# Main.net
KiCad netlist of a schematic drawn in Altium Designer
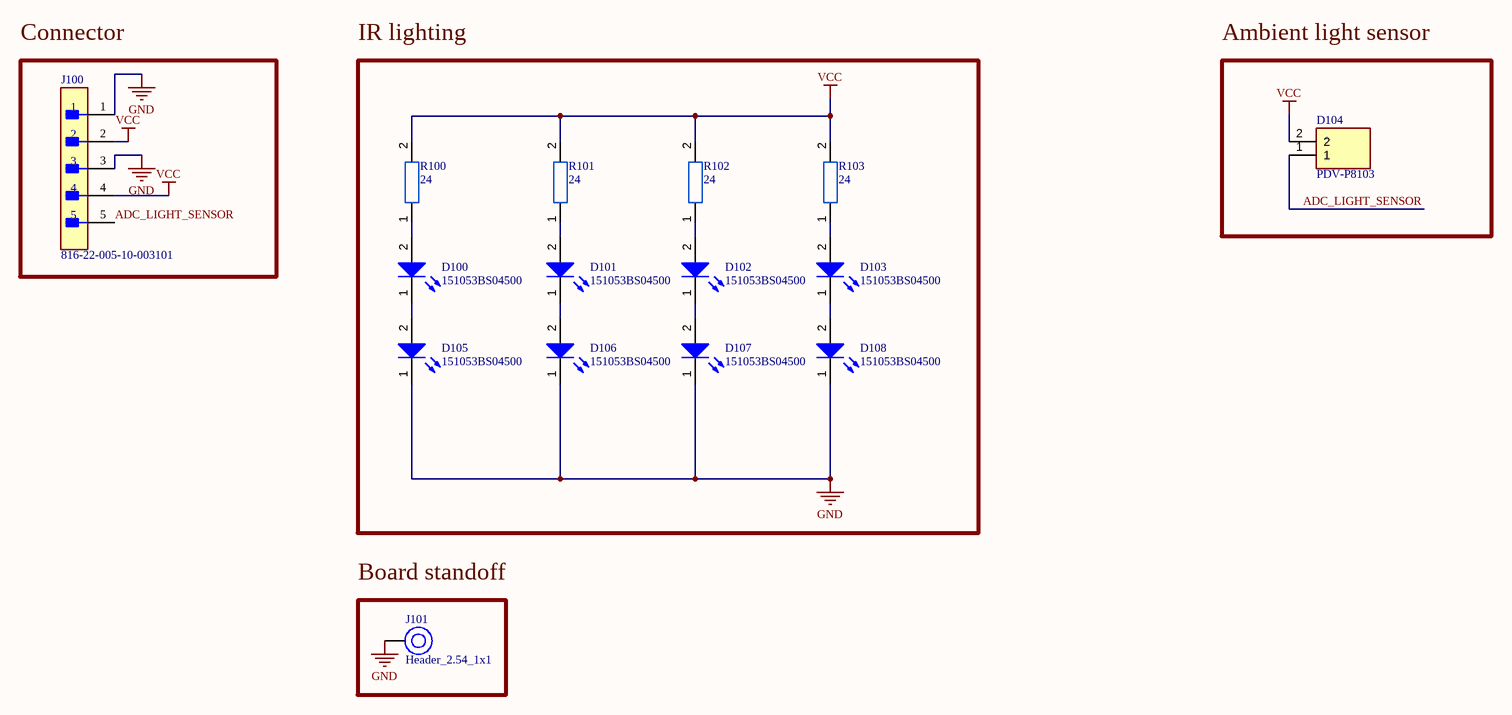
[diagram p0: Main.SchDoc]

(export (version "E")
  (design (tool "Eeschema 10.0.6"))
  (components
    (comp (ref "D100")
      (value "151053BS04500")
      (footprint "WL-TMRW_D5.8H11.7")
      (libsource (lib "Altium Content Vault") (part "LED_Blue_2A-1K"))
    )
    (comp (ref "D101")
      (value "151053BS04500")
      (footprint "WL-TMRW_D5.8H11.7")
      (libsource (lib "Altium Content Vault") (part "LED_Blue_2A-1K"))
    )
    (comp (ref "D102")
      (value "151053BS04500")
      (footprint "WL-TMRW_D5.8H11.7")
      (libsource (lib "Altium Content Vault") (part "LED_Blue_2A-1K"))
    )
    (comp (ref "D103")
      (value "151053BS04500")
      (footprint "WL-TMRW_D5.8H11.7")
      (description "https://www.lemona.lt/sviesos-diodas-o5mm-ir-skaidrus-30.html")
      (libsource (lib "Altium Content Vault") (part "LED_Blue_2A-1K"))
    )
    (comp (ref "D104")
      (value "PDV-P8103")
      (footprint "SamacSys:PDVP8103")
      (libsource (lib "*") (part "PDV-P8103"))
    )
    (comp (ref "D105")
      (value "151053BS04500")
      (footprint "WL-TMRW_D5.8H11.7")
      (libsource (lib "Altium Content Vault") (part "LED_Blue_2A-1K"))
    )
    (comp (ref "D106")
      (value "151053BS04500")
      (footprint "WL-TMRW_D5.8H11.7")
      (libsource (lib "Altium Content Vault") (part "LED_Blue_2A-1K"))
    )
    (comp (ref "D107")
      (value "151053BS04500")
      (footprint "WL-TMRW_D5.8H11.7")
      (libsource (lib "Altium Content Vault") (part "LED_Blue_2A-1K"))
    )
    (comp (ref "D108")
      (value "151053BS04500")
      (footprint "WL-TMRW_D5.8H11.7")
      (libsource (lib "Altium Content Vault") (part "LED_Blue_2A-1K"))
    )
    (comp (ref "J100")
      (value "816-22-005-10-003101")
      (footprint "FP-816-22-005-10-003101-MFG")
      (description "CONN SPRING PISTON 5POS PCB")
      (libsource (lib "Altium Content Vault") (part "bf93c07fd2649a848d0ec8585582aab"))
    )
    (comp (ref "J101")
      (value "Header_2.54_1x1")
      (footprint "HEADER_2.54_1x1")
      (libsource (lib "Schlib1") (part "Header_2.54_1x1"))
    )
    (comp (ref "R100")
      (value "24")
      (footprint "0402_footprint")
      (description "0402 resistor")
      (libsource (lib "Schlib1") (part "Resistor_0402"))
    )
    (comp (ref "R101")
      (value "24")
      (footprint "0402_footprint")
      (description "0402 resistor")
      (libsource (lib "Schlib1") (part "Resistor_0402"))
    )
    (comp (ref "R102")
      (value "24")
      (footprint "0402_footprint")
      (description "0402 resistor")
      (libsource (lib "Schlib1") (part "Resistor_0402"))
    )
    (comp (ref "R103")
      (value "24")
      (footprint "0402_footprint")
      (description "0402 resistor")
      (libsource (lib "Schlib1") (part "Resistor_0402"))
    )
  )
  (nets
    (net (code "1") (name "/ADC_LIGHT_SENSOR") (class "Default")
      (node (ref "D104") (pin "1") (pinfunction "1_1") (pintype "passive"))
      (node (ref "J100") (pin "5") (pinfunction "5_5") (pintype "passive"))
    )
    (net (code "2") (name "GND") (class "Default")
      (node (ref "D105") (pin "1") (pinfunction "K_1") (pintype "passive"))
      (node (ref "D106") (pin "1") (pinfunction "K_1") (pintype "passive"))
      (node (ref "D107") (pin "1") (pinfunction "K_1") (pintype "passive"))
      (node (ref "D108") (pin "1") (pinfunction "K_1") (pintype "passive"))
      (node (ref "J100") (pin "1") (pinfunction "1_1") (pintype "passive"))
      (node (ref "J100") (pin "3") (pinfunction "3_3") (pintype "passive"))
      (node (ref "J101") (pin "0") (pinfunction "0_0") (pintype "passive"))
    )
    (net (code "3") (name "Net-(D100-A)") (class "Default")
      (node (ref "D100") (pin "2") (pinfunction "A_2") (pintype "passive"))
      (node (ref "R100") (pin "1") (pinfunction "1_1") (pintype "passive"))
    )
    (net (code "4") (name "Net-(D100-K)") (class "Default")
      (node (ref "D100") (pin "1") (pinfunction "K_1") (pintype "passive"))
      (node (ref "D105") (pin "2") (pinfunction "A_2") (pintype "passive"))
    )
    (net (code "5") (name "Net-(D101-A)") (class "Default")
      (node (ref "D101") (pin "2") (pinfunction "A_2") (pintype "passive"))
      (node (ref "R101") (pin "1") (pinfunction "1_1") (pintype "passive"))
    )
    (net (code "6") (name "Net-(D101-K)") (class "Default")
      (node (ref "D101") (pin "1") (pinfunction "K_1") (pintype "passive"))
      (node (ref "D106") (pin "2") (pinfunction "A_2") (pintype "passive"))
    )
    (net (code "7") (name "Net-(D102-A)") (class "Default")
      (node (ref "D102") (pin "2") (pinfunction "A_2") (pintype "passive"))
      (node (ref "R102") (pin "1") (pinfunction "1_1") (pintype "passive"))
    )
    (net (code "8") (name "Net-(D102-K)") (class "Default")
      (node (ref "D102") (pin "1") (pinfunction "K_1") (pintype "passive"))
      (node (ref "D107") (pin "2") (pinfunction "A_2") (pintype "passive"))
    )
    (net (code "9") (name "Net-(D103-A)") (class "Default")
      (node (ref "D103") (pin "2") (pinfunction "A_2") (pintype "passive"))
      (node (ref "R103") (pin "1") (pinfunction "1_1") (pintype "passive"))
    )
    (net (code "10") (name "Net-(D103-K)") (class "Default")
      (node (ref "D103") (pin "1") (pinfunction "K_1") (pintype "passive"))
      (node (ref "D108") (pin "2") (pinfunction "A_2") (pintype "passive"))
    )
    (net (code "11") (name "VCC") (class "Default")
      (node (ref "D104") (pin "2") (pinfunction "2_2") (pintype "passive"))
      (node (ref "J100") (pin "2") (pinfunction "2_2") (pintype "passive"))
      (node (ref "J100") (pin "4") (pinfunction "4_4") (pintype "passive"))
      (node (ref "R100") (pin "2") (pinfunction "2_2") (pintype "passive"))
      (node (ref "R101") (pin "2") (pinfunction "2_2") (pintype "passive"))
      (node (ref "R102") (pin "2") (pinfunction "2_2") (pintype "passive"))
      (node (ref "R103") (pin "2") (pinfunction "2_2") (pintype "passive"))
    )
  )
)
